# Motor-Shield_v11.net
KiCad netlist of a schematic drawn in EAGLE
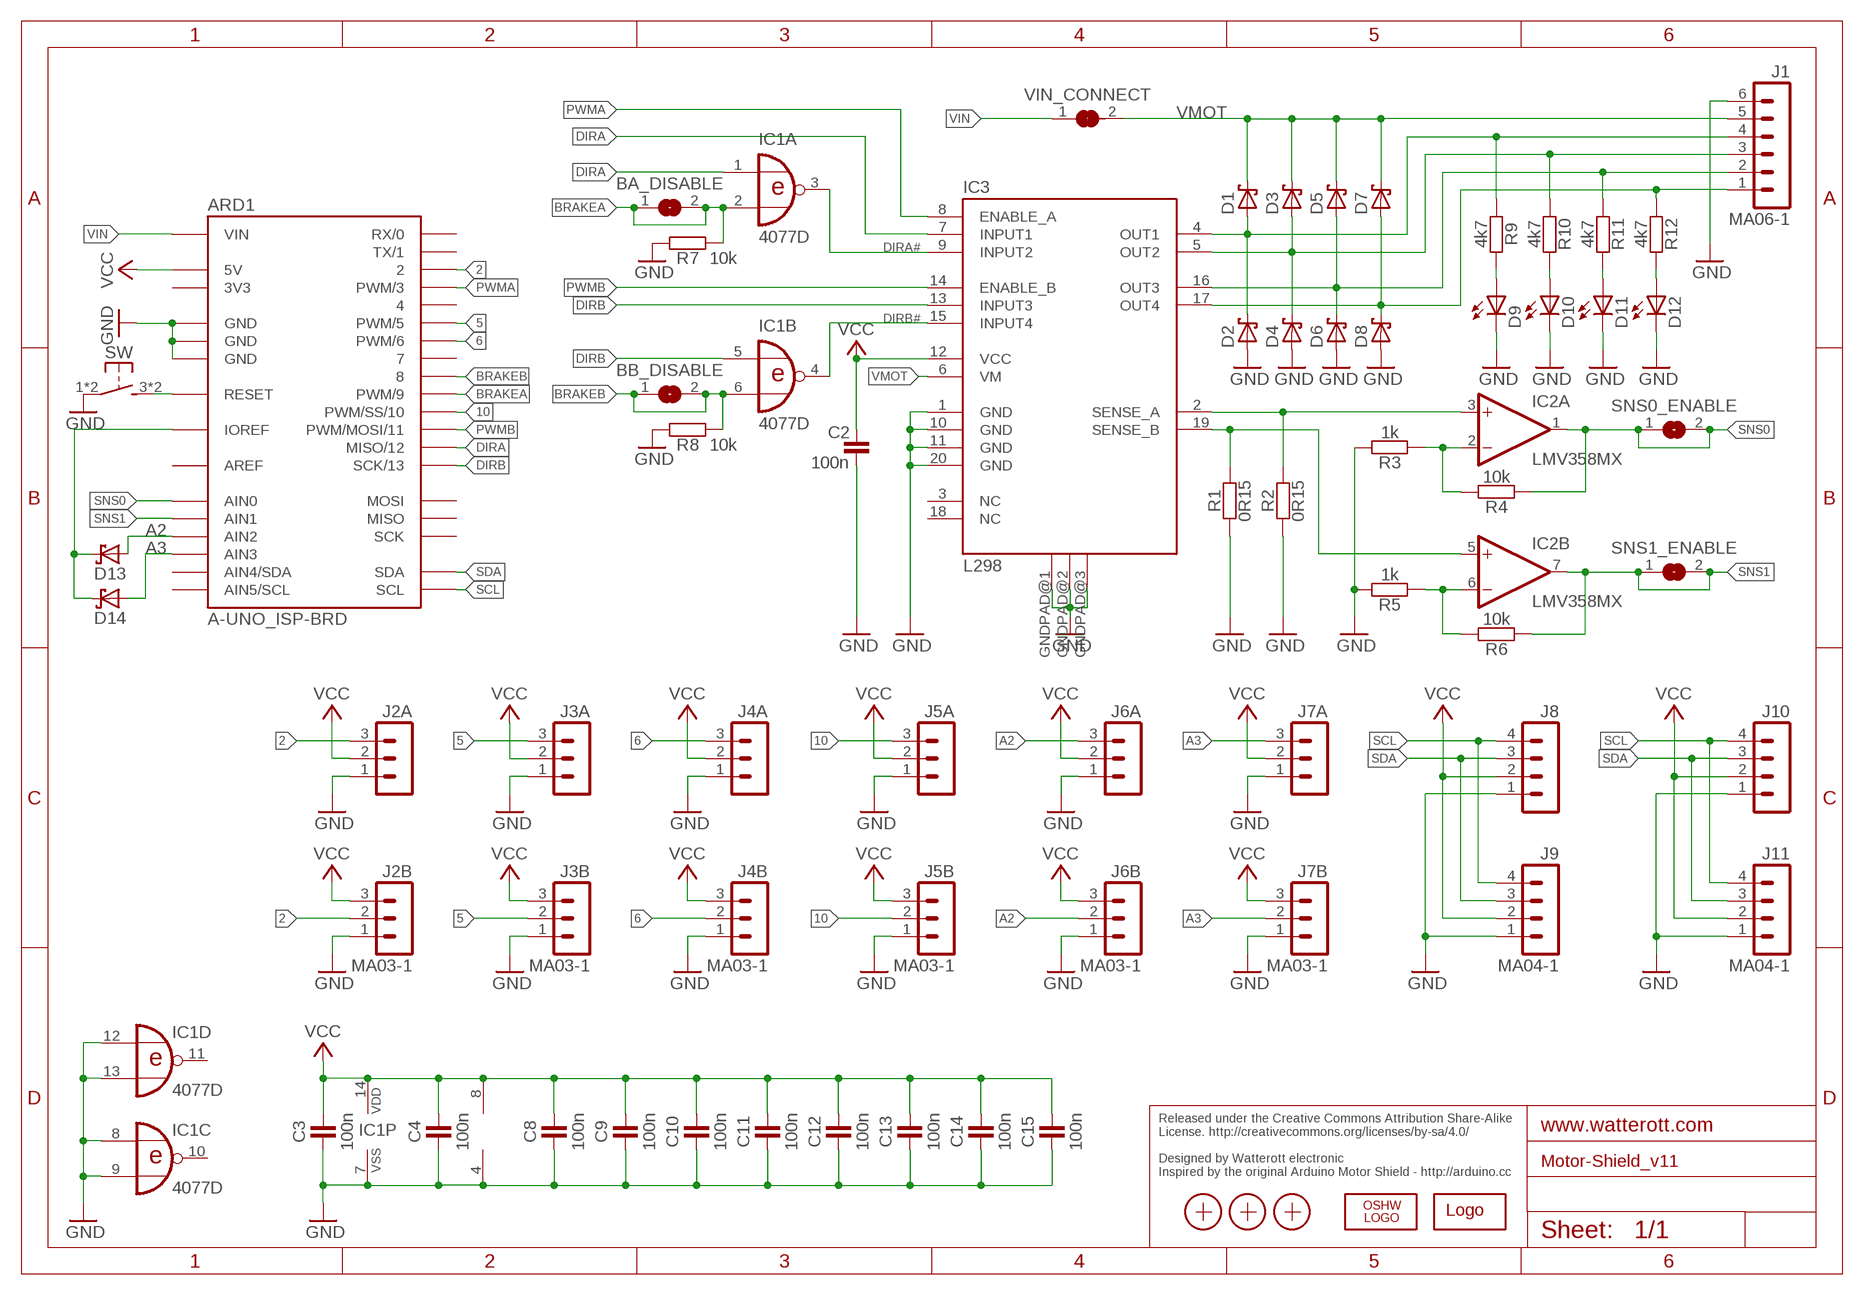
[diagram p0: schematic, sheet 1]

(export (version "E")
  (design (tool "Eeschema 10.0.6"))
  (components
    (comp (ref "ARD1")
      (value "A-UNO_ISP-BRD")
      (footprint "eagle-import:A-UNO-ISP")
      (libsource (lib "eagle-import") (part "A-UNO_ISP-BRD"))
    )
    (comp (ref "BA_DISABLE")
      (value "JUMPER2-0603")
      (footprint "eagle-import:JUMPER2-0603")
      (libsource (lib "eagle-import") (part "JUMPER2-0603"))
    )
    (comp (ref "BB_DISABLE")
      (value "JUMPER2-0603")
      (footprint "eagle-import:JUMPER2-0603")
      (libsource (lib "eagle-import") (part "JUMPER2-0603"))
    )
    (comp (ref "C2")
      (value "100n")
      (footprint "eagle-import:C0402")
      (libsource (lib "eagle-import") (part "CAPACITOR-0402"))
    )
    (comp (ref "C3")
      (value "100n")
      (footprint "eagle-import:C0402")
      (libsource (lib "eagle-import") (part "CAPACITOR-0402"))
    )
    (comp (ref "C4")
      (value "100n")
      (footprint "eagle-import:C0402")
      (libsource (lib "eagle-import") (part "CAPACITOR-0402"))
    )
    (comp (ref "C8")
      (value "100n")
      (footprint "eagle-import:C0402")
      (libsource (lib "eagle-import") (part "CAPACITOR-0402"))
    )
    (comp (ref "C9")
      (value "100n")
      (footprint "eagle-import:C0402")
      (libsource (lib "eagle-import") (part "CAPACITOR-0402"))
    )
    (comp (ref "C10")
      (value "100n")
      (footprint "eagle-import:C0402")
      (libsource (lib "eagle-import") (part "CAPACITOR-0402"))
    )
    (comp (ref "C11")
      (value "100n")
      (footprint "eagle-import:C0402")
      (libsource (lib "eagle-import") (part "CAPACITOR-0402"))
    )
    (comp (ref "C12")
      (value "100n")
      (footprint "eagle-import:C0402")
      (libsource (lib "eagle-import") (part "CAPACITOR-0402"))
    )
    (comp (ref "C13")
      (value "100n")
      (footprint "eagle-import:C0402")
      (libsource (lib "eagle-import") (part "CAPACITOR-0402"))
    )
    (comp (ref "C14")
      (value "100n")
      (footprint "eagle-import:C0402")
      (libsource (lib "eagle-import") (part "CAPACITOR-0402"))
    )
    (comp (ref "C15")
      (value "100n")
      (footprint "eagle-import:C0402")
      (libsource (lib "eagle-import") (part "CAPACITOR-0402"))
    )
    (comp (ref "D1")
      (value "D_SS14")
      (footprint "eagle-import:DO214AC")
      (libsource (lib "eagle-import") (part "D_SS14"))
    )
    (comp (ref "D2")
      (value "D_SS14")
      (footprint "eagle-import:DO214AC")
      (libsource (lib "eagle-import") (part "D_SS14"))
    )
    (comp (ref "D3")
      (value "D_SS14")
      (footprint "eagle-import:DO214AC")
      (libsource (lib "eagle-import") (part "D_SS14"))
    )
    (comp (ref "D4")
      (value "D_SS14")
      (footprint "eagle-import:DO214AC")
      (libsource (lib "eagle-import") (part "D_SS14"))
    )
    (comp (ref "D5")
      (value "D_SS14")
      (footprint "eagle-import:DO214AC")
      (libsource (lib "eagle-import") (part "D_SS14"))
    )
    (comp (ref "D6")
      (value "D_SS14")
      (footprint "eagle-import:DO214AC")
      (libsource (lib "eagle-import") (part "D_SS14"))
    )
    (comp (ref "D7")
      (value "D_SS14")
      (footprint "eagle-import:DO214AC")
      (libsource (lib "eagle-import") (part "D_SS14"))
    )
    (comp (ref "D8")
      (value "D_SS14")
      (footprint "eagle-import:DO214AC")
      (libsource (lib "eagle-import") (part "D_SS14"))
    )
    (comp (ref "D9")
      (value "LED-0603")
      (footprint "eagle-import:C0603")
      (libsource (lib "eagle-import") (part "LED-0603"))
    )
    (comp (ref "D10")
      (value "LED-0603")
      (footprint "eagle-import:C0603")
      (libsource (lib "eagle-import") (part "LED-0603"))
    )
    (comp (ref "D11")
      (value "LED-0603")
      (footprint "eagle-import:C0603")
      (libsource (lib "eagle-import") (part "LED-0603"))
    )
    (comp (ref "D12")
      (value "LED-0603")
      (footprint "eagle-import:C0603")
      (libsource (lib "eagle-import") (part "LED-0603"))
    )
    (comp (ref "D13")
      (value "D_SCHOTTKY-SOD110")
      (footprint "eagle-import:SOD110")
      (libsource (lib "eagle-import") (part "D_SCHOTTKY-SOD110"))
    )
    (comp (ref "D14")
      (value "D_SCHOTTKY-SOD110")
      (footprint "eagle-import:SOD110")
      (libsource (lib "eagle-import") (part "D_SCHOTTKY-SOD110"))
    )
    (comp (ref "IC1")
      (value "4077D")
      (footprint "eagle-import:SO14")
      (libsource (lib "eagle-import") (part "4077D"))
    )
    (comp (ref "IC2")
      (value "LMV358MX")
      (footprint "eagle-import:SO08")
      (libsource (lib "eagle-import") (part "LMV358?MX"))
    )
    (comp (ref "IC3")
      (value "L298")
      (footprint "eagle-import:POWERSO20")
      (libsource (lib "eagle-import") (part "L298"))
    )
    (comp (ref "J1")
      (value "MA06-1")
      (footprint "eagle-import:MA06-1")
      (libsource (lib "eagle-import") (part "MA06-1"))
    )
    (comp (ref "J2A")
      (value "JST_PH_3B3B-PH-SM4-TB")
      (footprint "eagle-import:JST_B3B-PH-SM4-TB")
      (libsource (lib "eagle-import") (part "JST_PH_3B3B-PH-SM4-TB"))
    )
    (comp (ref "J2B")
      (value "MA03-1")
      (footprint "eagle-import:MA03-1")
      (libsource (lib "eagle-import") (part "MA03-1"))
    )
    (comp (ref "J3A")
      (value "JST_PH_3B3B-PH-SM4-TB")
      (footprint "eagle-import:JST_B3B-PH-SM4-TB")
      (libsource (lib "eagle-import") (part "JST_PH_3B3B-PH-SM4-TB"))
    )
    (comp (ref "J3B")
      (value "MA03-1")
      (footprint "eagle-import:MA03-1")
      (libsource (lib "eagle-import") (part "MA03-1"))
    )
    (comp (ref "J4A")
      (value "JST_PH_3B3B-PH-SM4-TB")
      (footprint "eagle-import:JST_B3B-PH-SM4-TB")
      (libsource (lib "eagle-import") (part "JST_PH_3B3B-PH-SM4-TB"))
    )
    (comp (ref "J4B")
      (value "MA03-1")
      (footprint "eagle-import:MA03-1")
      (libsource (lib "eagle-import") (part "MA03-1"))
    )
    (comp (ref "J5A")
      (value "JST_PH_3B3B-PH-SM4-TB")
      (footprint "eagle-import:JST_B3B-PH-SM4-TB")
      (libsource (lib "eagle-import") (part "JST_PH_3B3B-PH-SM4-TB"))
    )
    (comp (ref "J5B")
      (value "MA03-1")
      (footprint "eagle-import:MA03-1")
      (libsource (lib "eagle-import") (part "MA03-1"))
    )
    (comp (ref "J6A")
      (value "JST_PH_3B3B-PH-SM4-TB")
      (footprint "eagle-import:JST_B3B-PH-SM4-TB")
      (libsource (lib "eagle-import") (part "JST_PH_3B3B-PH-SM4-TB"))
    )
    (comp (ref "J6B")
      (value "MA03-1")
      (footprint "eagle-import:MA03-1")
      (libsource (lib "eagle-import") (part "MA03-1"))
    )
    (comp (ref "J7A")
      (value "JST_PH_3B3B-PH-SM4-TB")
      (footprint "eagle-import:JST_B3B-PH-SM4-TB")
      (libsource (lib "eagle-import") (part "JST_PH_3B3B-PH-SM4-TB"))
    )
    (comp (ref "J7B")
      (value "MA03-1")
      (footprint "eagle-import:MA03-1")
      (libsource (lib "eagle-import") (part "MA03-1"))
    )
    (comp (ref "J8")
      (value "JST_PH_4B4B-PH-SM4-TB")
      (footprint "eagle-import:JST_B4B-PH-SM4-TB")
      (libsource (lib "eagle-import") (part "JST_PH_4B4B-PH-SM4-TB"))
    )
    (comp (ref "J9")
      (value "MA04-1")
      (footprint "eagle-import:MA04-1")
      (libsource (lib "eagle-import") (part "MA04-1"))
    )
    (comp (ref "J10")
      (value "JST_PH_4B4B-PH-SM4-TB")
      (footprint "eagle-import:JST_B4B-PH-SM4-TB")
      (libsource (lib "eagle-import") (part "JST_PH_4B4B-PH-SM4-TB"))
    )
    (comp (ref "J11")
      (value "MA04-1")
      (footprint "eagle-import:MA04-1")
      (libsource (lib "eagle-import") (part "MA04-1"))
    )
    (comp (ref "LOGO1")
      (value "LOGO-S_PLACE_S")
      (footprint "eagle-import:SPARK_TPLACE_S")
      (libsource (lib "eagle-import") (part "LOGO-S_PLACE_S"))
    )
    (comp (ref "LOGO2")
      (value "OSHW_LOGOX0070")
      (footprint "eagle-import:OSHW_6X70")
      (libsource (lib "eagle-import") (part "OSHW_LOGOX0070"))
    )
    (comp (ref "R1")
      (value "0R15")
      (footprint "eagle-import:C1206")
      (libsource (lib "eagle-import") (part "RESISTOR-1206"))
    )
    (comp (ref "R2")
      (value "0R15")
      (footprint "eagle-import:C1206")
      (libsource (lib "eagle-import") (part "RESISTOR-1206"))
    )
    (comp (ref "R3")
      (value "1k")
      (footprint "eagle-import:C0402")
      (libsource (lib "eagle-import") (part "RESISTOR-0402"))
    )
    (comp (ref "R4")
      (value "10k")
      (footprint "eagle-import:C0402")
      (libsource (lib "eagle-import") (part "RESISTOR-0402"))
    )
    (comp (ref "R5")
      (value "1k")
      (footprint "eagle-import:C0402")
      (libsource (lib "eagle-import") (part "RESISTOR-0402"))
    )
    (comp (ref "R6")
      (value "10k")
      (footprint "eagle-import:C0402")
      (libsource (lib "eagle-import") (part "RESISTOR-0402"))
    )
    (comp (ref "R7")
      (value "10k")
      (footprint "eagle-import:C0402")
      (libsource (lib "eagle-import") (part "RESISTOR-0402"))
    )
    (comp (ref "R8")
      (value "10k")
      (footprint "eagle-import:C0402")
      (libsource (lib "eagle-import") (part "RESISTOR-0402"))
    )
    (comp (ref "R9")
      (value "4k7")
      (footprint "eagle-import:C0402")
      (libsource (lib "eagle-import") (part "RESISTOR-0402"))
    )
    (comp (ref "R10")
      (value "4k7")
      (footprint "eagle-import:C0402")
      (libsource (lib "eagle-import") (part "RESISTOR-0402"))
    )
    (comp (ref "R11")
      (value "4k7")
      (footprint "eagle-import:C0402")
      (libsource (lib "eagle-import") (part "RESISTOR-0402"))
    )
    (comp (ref "R12")
      (value "4k7")
      (footprint "eagle-import:C0402")
      (libsource (lib "eagle-import") (part "RESISTOR-0402"))
    )
    (comp (ref "SNS0_ENABLE")
      (value "JUMPER2-0603")
      (footprint "eagle-import:JUMPER2-0603")
      (libsource (lib "eagle-import") (part "JUMPER2-0603"))
    )
    (comp (ref "SNS1_ENABLE")
      (value "JUMPER2-0603")
      (footprint "eagle-import:JUMPER2-0603")
      (libsource (lib "eagle-import") (part "JUMPER2-0603"))
    )
    (comp (ref "SW")
      (value "SW-TACTILE-6X6_SMD")
      (footprint "eagle-import:SW6X6_SMD")
      (libsource (lib "eagle-import") (part "SW-TACTILE-6X6_SMD"))
    )
    (comp (ref "VIN_CONNECT")
      (value "JUMPER2-0603")
      (footprint "eagle-import:JUMPER2-0603")
      (libsource (lib "eagle-import") (part "JUMPER2-0603"))
    )
    (comp (ref "X1")
      (value "PASSER-07")
      (footprint "eagle-import:PASSER_07MM")
      (libsource (lib "eagle-import") (part "PASSER-07"))
    )
    (comp (ref "X2")
      (value "PASSER-07")
      (footprint "eagle-import:PASSER_07MM")
      (libsource (lib "eagle-import") (part "PASSER-07"))
    )
    (comp (ref "X3")
      (value "PASSER-07")
      (footprint "eagle-import:PASSER_07MM")
      (libsource (lib "eagle-import") (part "PASSER-07"))
    )
  )
  (nets
    (net (code "1") (name "/3V3") (class "Default")
      (node (ref "ARD1") (pin "3V3") (pinfunction "3V3_3V3") (pintype "power_in"))
    )
    (net (code "2") (name "/AREF") (class "Default")
      (node (ref "ARD1") (pin "AREF") (pinfunction "AREF_AREF") (pintype "power_in"))
    )
    (net (code "3") (name "/DIRA#") (class "Default")
      (node (ref "IC1") (pin "3") (pinfunction "O_3") (pintype "output"))
      (node (ref "IC3") (pin "9") (pinfunction "INPUT2_9") (pintype "input"))
    )
    (net (code "4") (name "/DIRB#") (class "Default")
      (node (ref "IC1") (pin "4") (pinfunction "O_4") (pintype "output"))
      (node (ref "IC3") (pin "15") (pinfunction "INPUT4_15") (pintype "input"))
    )
    (net (code "5") (name "2") (class "Default")
      (node (ref "ARD1") (pin "2") (pinfunction "2_2") (pintype "bidirectional"))
      (node (ref "J2A") (pin "3") (pinfunction "3_3") (pintype "passive"))
      (node (ref "J2B") (pin "2") (pinfunction "2_2") (pintype "passive"))
    )
    (net (code "6") (name "5") (class "Default")
      (node (ref "ARD1") (pin "5") (pinfunction "PWM/5_5") (pintype "bidirectional"))
      (node (ref "J3A") (pin "3") (pinfunction "3_3") (pintype "passive"))
      (node (ref "J3B") (pin "2") (pinfunction "2_2") (pintype "passive"))
    )
    (net (code "7") (name "6") (class "Default")
      (node (ref "ARD1") (pin "6") (pinfunction "PWM/6_6") (pintype "bidirectional"))
      (node (ref "J4A") (pin "3") (pinfunction "3_3") (pintype "passive"))
      (node (ref "J4B") (pin "2") (pinfunction "2_2") (pintype "passive"))
    )
    (net (code "8") (name "10") (class "Default")
      (node (ref "ARD1") (pin "10") (pinfunction "PWM/SS/10_10") (pintype "bidirectional"))
      (node (ref "J5A") (pin "3") (pinfunction "3_3") (pintype "passive"))
      (node (ref "J5B") (pin "2") (pinfunction "2_2") (pintype "passive"))
    )
    (net (code "9") (name "A2") (class "Default")
      (node (ref "ARD1") (pin "A2") (pinfunction "AIN2_A2") (pintype "bidirectional"))
      (node (ref "D13") (pin "A") (pinfunction "A_A") (pintype "passive"))
      (node (ref "J6A") (pin "3") (pinfunction "3_3") (pintype "passive"))
      (node (ref "J6B") (pin "2") (pinfunction "2_2") (pintype "passive"))
    )
    (net (code "10") (name "A3") (class "Default")
      (node (ref "ARD1") (pin "A3") (pinfunction "AIN3_A3") (pintype "bidirectional"))
      (node (ref "D14") (pin "A") (pinfunction "A_A") (pintype "passive"))
      (node (ref "J7A") (pin "3") (pinfunction "3_3") (pintype "passive"))
      (node (ref "J7B") (pin "2") (pinfunction "2_2") (pintype "passive"))
    )
    (net (code "11") (name "BRAKEA") (class "Default")
      (node (ref "ARD1") (pin "9") (pinfunction "PWM/9_9") (pintype "bidirectional"))
      (node (ref "BA_DISABLE") (pin "1") (pinfunction "1_1") (pintype "passive"))
      (node (ref "BA_DISABLE") (pin "2") (pinfunction "2_2") (pintype "passive"))
      (node (ref "IC1") (pin "2") (pinfunction "I1_2") (pintype "input"))
      (node (ref "R7") (pin "1") (pinfunction "1_1") (pintype "passive"))
    )
    (net (code "12") (name "BRAKEB") (class "Default")
      (node (ref "ARD1") (pin "8") (pinfunction "8_8") (pintype "bidirectional"))
      (node (ref "BB_DISABLE") (pin "1") (pinfunction "1_1") (pintype "passive"))
      (node (ref "BB_DISABLE") (pin "2") (pinfunction "2_2") (pintype "passive"))
      (node (ref "IC1") (pin "6") (pinfunction "I1_6") (pintype "input"))
      (node (ref "R8") (pin "1") (pinfunction "1_1") (pintype "passive"))
    )
    (net (code "13") (name "DIRA") (class "Default")
      (node (ref "ARD1") (pin "12") (pinfunction "MISO/12_12") (pintype "bidirectional"))
      (node (ref "IC1") (pin "1") (pinfunction "I0_1") (pintype "input"))
      (node (ref "IC3") (pin "7") (pinfunction "INPUT1_7") (pintype "input"))
    )
    (net (code "14") (name "DIRB") (class "Default")
      (node (ref "ARD1") (pin "13") (pinfunction "SCK/13_13") (pintype "bidirectional"))
      (node (ref "IC1") (pin "5") (pinfunction "I0_5") (pintype "input"))
      (node (ref "IC3") (pin "13") (pinfunction "INPUT3_13") (pintype "input"))
    )
    (net (code "15") (name "GND") (class "Default")
      (node (ref "ARD1") (pin "GND@1") (pinfunction "GND_GND@1") (pintype "power_in"))
      (node (ref "ARD1") (pin "GND@2") (pinfunction "GND_GND@2") (pintype "power_in"))
      (node (ref "ARD1") (pin "GND@3") (pinfunction "GND_GND@3") (pintype "power_in"))
      (node (ref "ARD1") (pin "GND@4") (pinfunction "GND_GND@4") (pintype "power_in"))
      (node (ref "C10") (pin "1") (pinfunction "1_1") (pintype "passive"))
      (node (ref "C11") (pin "1") (pinfunction "1_1") (pintype "passive"))
      (node (ref "C12") (pin "1") (pinfunction "1_1") (pintype "passive"))
      (node (ref "C13") (pin "1") (pinfunction "1_1") (pintype "passive"))
      (node (ref "C14") (pin "1") (pinfunction "1_1") (pintype "passive"))
      (node (ref "C15") (pin "1") (pinfunction "1_1") (pintype "passive"))
      (node (ref "C2") (pin "1") (pinfunction "1_1") (pintype "passive"))
      (node (ref "C3") (pin "1") (pinfunction "1_1") (pintype "passive"))
      (node (ref "C4") (pin "1") (pinfunction "1_1") (pintype "passive"))
      (node (ref "C8") (pin "1") (pinfunction "1_1") (pintype "passive"))
      (node (ref "C9") (pin "1") (pinfunction "1_1") (pintype "passive"))
      (node (ref "D10") (pin "C") (pinfunction "C_C") (pintype "passive"))
      (node (ref "D11") (pin "C") (pinfunction "C_C") (pintype "passive"))
      (node (ref "D12") (pin "C") (pinfunction "C_C") (pintype "passive"))
      (node (ref "D2") (pin "1") (pinfunction "A_1") (pintype "passive"))
      (node (ref "D4") (pin "1") (pinfunction "A_1") (pintype "passive"))
      (node (ref "D6") (pin "1") (pinfunction "A_1") (pintype "passive"))
      (node (ref "D8") (pin "1") (pinfunction "A_1") (pintype "passive"))
      (node (ref "D9") (pin "C") (pinfunction "C_C") (pintype "passive"))
      (node (ref "IC1") (pin "12") (pinfunction "I0_12") (pintype "input"))
      (node (ref "IC1") (pin "13") (pinfunction "I1_13") (pintype "input"))
      (node (ref "IC1") (pin "7") (pinfunction "VSS_7") (pintype "power_in"))
      (node (ref "IC1") (pin "8") (pinfunction "I0_8") (pintype "input"))
      (node (ref "IC1") (pin "9") (pinfunction "I1_9") (pintype "input"))
      (node (ref "IC2") (pin "4") (pinfunction "V-_4") (pintype "power_in"))
      (node (ref "IC3") (pin "1") (pinfunction "GND_1") (pintype "power_in"))
      (node (ref "IC3") (pin "10") (pinfunction "GND_10") (pintype "power_in"))
      (node (ref "IC3") (pin "11") (pinfunction "GND_11") (pintype "power_in"))
      (node (ref "IC3") (pin "20") (pinfunction "GND_20") (pintype "power_in"))
      (node (ref "IC3") (pin "GNDPAD@1") (pinfunction "GNDPAD_GNDPAD@1") (pintype "power_in"))
      (node (ref "IC3") (pin "GNDPAD@2") (pinfunction "GNDPAD_GNDPAD@2") (pintype "power_in"))
      (node (ref "IC3") (pin "GNDPAD@3") (pinfunction "GNDPAD_GNDPAD@3") (pintype "power_in"))
      (node (ref "J1") (pin "6") (pinfunction "6_6") (pintype "passive"))
      (node (ref "J10") (pin "1") (pinfunction "1_1") (pintype "passive"))
      (node (ref "J11") (pin "1") (pinfunction "1_1") (pintype "passive"))
      (node (ref "J2A") (pin "1") (pinfunction "1_1") (pintype "passive"))
      (node (ref "J2B") (pin "1") (pinfunction "1_1") (pintype "passive"))
      (node (ref "J3A") (pin "1") (pinfunction "1_1") (pintype "passive"))
      (node (ref "J3B") (pin "1") (pinfunction "1_1") (pintype "passive"))
      (node (ref "J4A") (pin "1") (pinfunction "1_1") (pintype "passive"))
      (node (ref "J4B") (pin "1") (pinfunction "1_1") (pintype "passive"))
      (node (ref "J5A") (pin "1") (pinfunction "1_1") (pintype "passive"))
      (node (ref "J5B") (pin "1") (pinfunction "1_1") (pintype "passive"))
      (node (ref "J6A") (pin "1") (pinfunction "1_1") (pintype "passive"))
      (node (ref "J6B") (pin "1") (pinfunction "1_1") (pintype "passive"))
      (node (ref "J7A") (pin "1") (pinfunction "1_1") (pintype "passive"))
      (node (ref "J7B") (pin "1") (pinfunction "1_1") (pintype "passive"))
      (node (ref "J8") (pin "1") (pinfunction "1_1") (pintype "passive"))
      (node (ref "J9") (pin "1") (pinfunction "1_1") (pintype "passive"))
      (node (ref "R1") (pin "1") (pinfunction "1_1") (pintype "passive"))
      (node (ref "R2") (pin "1") (pinfunction "1_1") (pintype "passive"))
      (node (ref "R3") (pin "2") (pinfunction "2_2") (pintype "passive"))
      (node (ref "R5") (pin "2") (pinfunction "2_2") (pintype "passive"))
      (node (ref "R7") (pin "2") (pinfunction "2_2") (pintype "passive"))
      (node (ref "R8") (pin "2") (pinfunction "2_2") (pintype "passive"))
      (node (ref "SW") (pin "1") (pinfunction "P1_1") (pintype "passive"))
      (node (ref "SW") (pin "2") (pinfunction "P1_2") (pintype "passive"))
    )
    (net (code "16") (name "Net-(ARD1-PadIOREF)") (class "Default")
      (node (ref "ARD1") (pin "IOREF") (pinfunction "IOREF_IOREF") (pintype "power_in"))
      (node (ref "D13") (pin "C") (pinfunction "C_C") (pintype "passive"))
      (node (ref "D14") (pin "C") (pinfunction "C_C") (pintype "passive"))
    )
    (net (code "17") (name "Net-(ARD1-RESET-PadRST@1)") (class "Default")
      (node (ref "ARD1") (pin "RST@1") (pinfunction "RESET_RST@1") (pintype "bidirectional"))
      (node (ref "ARD1") (pin "RST@2") (pinfunction "RESET_RST@2") (pintype "bidirectional"))
      (node (ref "SW") (pin "3") (pinfunction "S1_3") (pintype "passive"))
      (node (ref "SW") (pin "4") (pinfunction "S1_4") (pintype "passive"))
    )
    (net (code "18") (name "Net-(D1-A)") (class "Default")
      (node (ref "D1") (pin "1") (pinfunction "A_1") (pintype "passive"))
      (node (ref "D2") (pin "2") (pinfunction "C_2") (pintype "passive"))
      (node (ref "IC3") (pin "4") (pinfunction "OUT1_4") (pintype "output"))
      (node (ref "J1") (pin "4") (pinfunction "4_4") (pintype "passive"))
      (node (ref "R9") (pin "1") (pinfunction "1_1") (pintype "passive"))
    )
    (net (code "19") (name "Net-(D3-A)") (class "Default")
      (node (ref "D3") (pin "1") (pinfunction "A_1") (pintype "passive"))
      (node (ref "D4") (pin "2") (pinfunction "C_2") (pintype "passive"))
      (node (ref "IC3") (pin "5") (pinfunction "OUT2_5") (pintype "output"))
      (node (ref "J1") (pin "3") (pinfunction "3_3") (pintype "passive"))
      (node (ref "R10") (pin "1") (pinfunction "1_1") (pintype "passive"))
    )
    (net (code "20") (name "Net-(D5-A)") (class "Default")
      (node (ref "D5") (pin "1") (pinfunction "A_1") (pintype "passive"))
      (node (ref "D6") (pin "2") (pinfunction "C_2") (pintype "passive"))
      (node (ref "IC3") (pin "16") (pinfunction "OUT3_16") (pintype "output"))
      (node (ref "J1") (pin "2") (pinfunction "2_2") (pintype "passive"))
      (node (ref "R11") (pin "1") (pinfunction "1_1") (pintype "passive"))
    )
    (net (code "21") (name "Net-(D7-A)") (class "Default")
      (node (ref "D7") (pin "1") (pinfunction "A_1") (pintype "passive"))
      (node (ref "D8") (pin "2") (pinfunction "C_2") (pintype "passive"))
      (node (ref "IC3") (pin "17") (pinfunction "OUT4_17") (pintype "output"))
      (node (ref "J1") (pin "1") (pinfunction "1_1") (pintype "passive"))
      (node (ref "R12") (pin "1") (pinfunction "1_1") (pintype "passive"))
    )
    (net (code "22") (name "Net-(D9-PadA)") (class "Default")
      (node (ref "D9") (pin "A") (pinfunction "A_A") (pintype "passive"))
      (node (ref "R9") (pin "2") (pinfunction "2_2") (pintype "passive"))
    )
    (net (code "23") (name "Net-(D10-PadA)") (class "Default")
      (node (ref "D10") (pin "A") (pinfunction "A_A") (pintype "passive"))
      (node (ref "R10") (pin "2") (pinfunction "2_2") (pintype "passive"))
    )
    (net (code "24") (name "Net-(D11-PadA)") (class "Default")
      (node (ref "D11") (pin "A") (pinfunction "A_A") (pintype "passive"))
      (node (ref "R11") (pin "2") (pinfunction "2_2") (pintype "passive"))
    )
    (net (code "25") (name "Net-(D12-PadA)") (class "Default")
      (node (ref "D12") (pin "A") (pinfunction "A_A") (pintype "passive"))
      (node (ref "R12") (pin "2") (pinfunction "2_2") (pintype "passive"))
    )
    (net (code "26") (name "Net-(IC2A-+IN)") (class "Default")
      (node (ref "IC2") (pin "3") (pinfunction "+IN_3") (pintype "input"))
      (node (ref "IC3") (pin "2") (pinfunction "SENSE_A_2") (pintype "output"))
      (node (ref "R2") (pin "2") (pinfunction "2_2") (pintype "passive"))
    )
    (net (code "27") (name "Net-(IC2A--IN)") (class "Default")
      (node (ref "IC2") (pin "2") (pinfunction "-IN_2") (pintype "input"))
      (node (ref "R3") (pin "1") (pinfunction "1_1") (pintype "passive"))
      (node (ref "R4") (pin "2") (pinfunction "2_2") (pintype "passive"))
    )
    (net (code "28") (name "Net-(IC2B-+IN)") (class "Default")
      (node (ref "IC2") (pin "5") (pinfunction "+IN_5") (pintype "input"))
      (node (ref "IC3") (pin "19") (pinfunction "SENSE_B_19") (pintype "output"))
      (node (ref "R1") (pin "2") (pinfunction "2_2") (pintype "passive"))
    )
    (net (code "29") (name "Net-(IC2B--IN)") (class "Default")
      (node (ref "IC2") (pin "6") (pinfunction "-IN_6") (pintype "input"))
      (node (ref "R5") (pin "1") (pinfunction "1_1") (pintype "passive"))
      (node (ref "R6") (pin "2") (pinfunction "2_2") (pintype "passive"))
    )
    (net (code "30") (name "PWMA") (class "Default")
      (node (ref "ARD1") (pin "3") (pinfunction "PWM/3_3") (pintype "bidirectional"))
      (node (ref "IC3") (pin "8") (pinfunction "ENABLE_A_8") (pintype "input"))
    )
    (net (code "31") (name "PWMB") (class "Default")
      (node (ref "ARD1") (pin "11") (pinfunction "PWM/MOSI/11_11") (pintype "bidirectional"))
      (node (ref "IC3") (pin "14") (pinfunction "ENABLE_B_14") (pintype "input"))
    )
    (net (code "32") (name "SCL") (class "Default")
      (node (ref "ARD1") (pin "SCL") (pinfunction "SCL_SCL") (pintype "bidirectional"))
      (node (ref "J10") (pin "4") (pinfunction "4_4") (pintype "passive"))
      (node (ref "J11") (pin "4") (pinfunction "4_4") (pintype "passive"))
      (node (ref "J8") (pin "4") (pinfunction "4_4") (pintype "passive"))
      (node (ref "J9") (pin "4") (pinfunction "4_4") (pintype "passive"))
    )
    (net (code "33") (name "SDA") (class "Default")
      (node (ref "ARD1") (pin "SDA") (pinfunction "SDA_SDA") (pintype "bidirectional"))
      (node (ref "J10") (pin "3") (pinfunction "3_3") (pintype "passive"))
      (node (ref "J11") (pin "3") (pinfunction "3_3") (pintype "passive"))
      (node (ref "J8") (pin "3") (pinfunction "3_3") (pintype "passive"))
      (node (ref "J9") (pin "3") (pinfunction "3_3") (pintype "passive"))
    )
    (net (code "34") (name "SNS0") (class "Default")
      (node (ref "ARD1") (pin "A0") (pinfunction "AIN0_A0") (pintype "bidirectional"))
      (node (ref "IC2") (pin "1") (pinfunction "OUT_1") (pintype "output"))
      (node (ref "R4") (pin "1") (pinfunction "1_1") (pintype "passive"))
      (node (ref "SNS0_ENABLE") (pin "1") (pinfunction "1_1") (pintype "passive"))
      (node (ref "SNS0_ENABLE") (pin "2") (pinfunction "2_2") (pintype "passive"))
    )
    (net (code "35") (name "SNS1") (class "Default")
      (node (ref "ARD1") (pin "A1") (pinfunction "AIN1_A1") (pintype "bidirectional"))
      (node (ref "IC2") (pin "7") (pinfunction "OUT_7") (pintype "output"))
      (node (ref "R6") (pin "1") (pinfunction "1_1") (pintype "passive"))
      (node (ref "SNS1_ENABLE") (pin "1") (pinfunction "1_1") (pintype "passive"))
      (node (ref "SNS1_ENABLE") (pin "2") (pinfunction "2_2") (pintype "passive"))
    )
    (net (code "36") (name "VCC") (class "Default")
      (node (ref "ARD1") (pin "5V") (pinfunction "5V_5V") (pintype "power_in"))
      (node (ref "ARD1") (pin "VCC") (pinfunction "5V_VCC") (pintype "power_in"))
      (node (ref "C10") (pin "2") (pinfunction "2_2") (pintype "passive"))
      (node (ref "C11") (pin "2") (pinfunction "2_2") (pintype "passive"))
      (node (ref "C12") (pin "2") (pinfunction "2_2") (pintype "passive"))
      (node (ref "C13") (pin "2") (pinfunction "2_2") (pintype "passive"))
      (node (ref "C14") (pin "2") (pinfunction "2_2") (pintype "passive"))
      (node (ref "C15") (pin "2") (pinfunction "2_2") (pintype "passive"))
      (node (ref "C2") (pin "2") (pinfunction "2_2") (pintype "passive"))
      (node (ref "C3") (pin "2") (pinfunction "2_2") (pintype "passive"))
      (node (ref "C4") (pin "2") (pinfunction "2_2") (pintype "passive"))
      (node (ref "C8") (pin "2") (pinfunction "2_2") (pintype "passive"))
      (node (ref "C9") (pin "2") (pinfunction "2_2") (pintype "passive"))
      (node (ref "IC1") (pin "14") (pinfunction "VDD_14") (pintype "power_in"))
      (node (ref "IC2") (pin "8") (pinfunction "V+_8") (pintype "power_in"))
      (node (ref "IC3") (pin "12") (pinfunction "VCC_12") (pintype "power_in"))
      (node (ref "J10") (pin "2") (pinfunction "2_2") (pintype "passive"))
      (node (ref "J11") (pin "2") (pinfunction "2_2") (pintype "passive"))
      (node (ref "J2A") (pin "2") (pinfunction "2_2") (pintype "passive"))
      (node (ref "J2B") (pin "3") (pinfunction "3_3") (pintype "passive"))
      (node (ref "J3A") (pin "2") (pinfunction "2_2") (pintype "passive"))
      (node (ref "J3B") (pin "3") (pinfunction "3_3") (pintype "passive"))
      (node (ref "J4A") (pin "2") (pinfunction "2_2") (pintype "passive"))
      (node (ref "J4B") (pin "3") (pinfunction "3_3") (pintype "passive"))
      (node (ref "J5A") (pin "2") (pinfunction "2_2") (pintype "passive"))
      (node (ref "J5B") (pin "3") (pinfunction "3_3") (pintype "passive"))
      (node (ref "J6A") (pin "2") (pinfunction "2_2") (pintype "passive"))
      (node (ref "J6B") (pin "3") (pinfunction "3_3") (pintype "passive"))
      (node (ref "J7A") (pin "2") (pinfunction "2_2") (pintype "passive"))
      (node (ref "J7B") (pin "3") (pinfunction "3_3") (pintype "passive"))
      (node (ref "J8") (pin "2") (pinfunction "2_2") (pintype "passive"))
      (node (ref "J9") (pin "2") (pinfunction "2_2") (pintype "passive"))
    )
    (net (code "37") (name "VIN") (class "Default")
      (node (ref "ARD1") (pin "VIN") (pinfunction "VIN_VIN") (pintype "power_in"))
      (node (ref "VIN_CONNECT") (pin "1") (pinfunction "1_1") (pintype "passive"))
    )
    (net (code "38") (name "VMOT") (class "Default")
      (node (ref "D1") (pin "2") (pinfunction "C_2") (pintype "passive"))
      (node (ref "D3") (pin "2") (pinfunction "C_2") (pintype "passive"))
      (node (ref "D5") (pin "2") (pinfunction "C_2") (pintype "passive"))
      (node (ref "D7") (pin "2") (pinfunction "C_2") (pintype "passive"))
      (node (ref "IC3") (pin "6") (pinfunction "VM_6") (pintype "power_in"))
      (node (ref "J1") (pin "5") (pinfunction "5_5") (pintype "passive"))
      (node (ref "VIN_CONNECT") (pin "2") (pinfunction "2_2") (pintype "passive"))
    )
    (net (code "39") (name "unconnected-(ARD1-AIN4{slash}SDA-PadA4)") (class "Default")
      (node (ref "ARD1") (pin "A4") (pinfunction "AIN4/SDA_A4") (pintype "bidirectional"))
    )
    (net (code "40") (name "unconnected-(ARD1-AIN5{slash}SCL-PadA5)") (class "Default")
      (node (ref "ARD1") (pin "A5") (pinfunction "AIN5/SCL_A5") (pintype "bidirectional"))
    )
    (net (code "41") (name "unconnected-(ARD1-Pad4)") (class "Default")
      (node (ref "ARD1") (pin "4") (pinfunction "4_4") (pintype "bidirectional"))
    )
    (net (code "42") (name "unconnected-(ARD1-Pad7)") (class "Default")
      (node (ref "ARD1") (pin "7") (pinfunction "7_7") (pintype "bidirectional"))
    )
    (net (code "43") (name "unconnected-(ARD1-PadMISO)") (class "Default")
      (node (ref "ARD1") (pin "MISO") (pinfunction "MISO_MISO") (pintype "bidirectional"))
    )
    (net (code "44") (name "unconnected-(ARD1-PadMOSI)") (class "Default")
      (node (ref "ARD1") (pin "MOSI") (pinfunction "MOSI_MOSI") (pintype "bidirectional"))
    )
    (net (code "45") (name "unconnected-(ARD1-PadSCK)") (class "Default")
      (node (ref "ARD1") (pin "SCK") (pinfunction "SCK_SCK") (pintype "bidirectional"))
    )
    (net (code "46") (name "unconnected-(ARD1-RX{slash}0-Pad0)") (class "Default")
      (node (ref "ARD1") (pin "0") (pinfunction "RX/0_0") (pintype "bidirectional"))
    )
    (net (code "47") (name "unconnected-(ARD1-TX{slash}1-Pad1)") (class "Default")
      (node (ref "ARD1") (pin "1") (pinfunction "TX/1_1") (pintype "bidirectional"))
    )
    (net (code "48") (name "unconnected-(IC1C-O-Pad10)") (class "Default")
      (node (ref "IC1") (pin "10") (pinfunction "O_10") (pintype "output"))
    )
    (net (code "49") (name "unconnected-(IC1D-O-Pad11)") (class "Default")
      (node (ref "IC1") (pin "11") (pinfunction "O_11") (pintype "output"))
    )
    (net (code "50") (name "unconnected-(IC3-NC-Pad3)") (class "Default")
      (node (ref "IC3") (pin "3") (pinfunction "NC_3") (pintype "no_connect"))
    )
    (net (code "51") (name "unconnected-(IC3-NC-Pad18)") (class "Default")
      (node (ref "IC3") (pin "18") (pinfunction "NC_18") (pintype "no_connect"))
    )
  )
)
